# SCH_pie-day-pcb_2024-03-26.net
KiCad netlist of a schematic drawn in EasyEDA
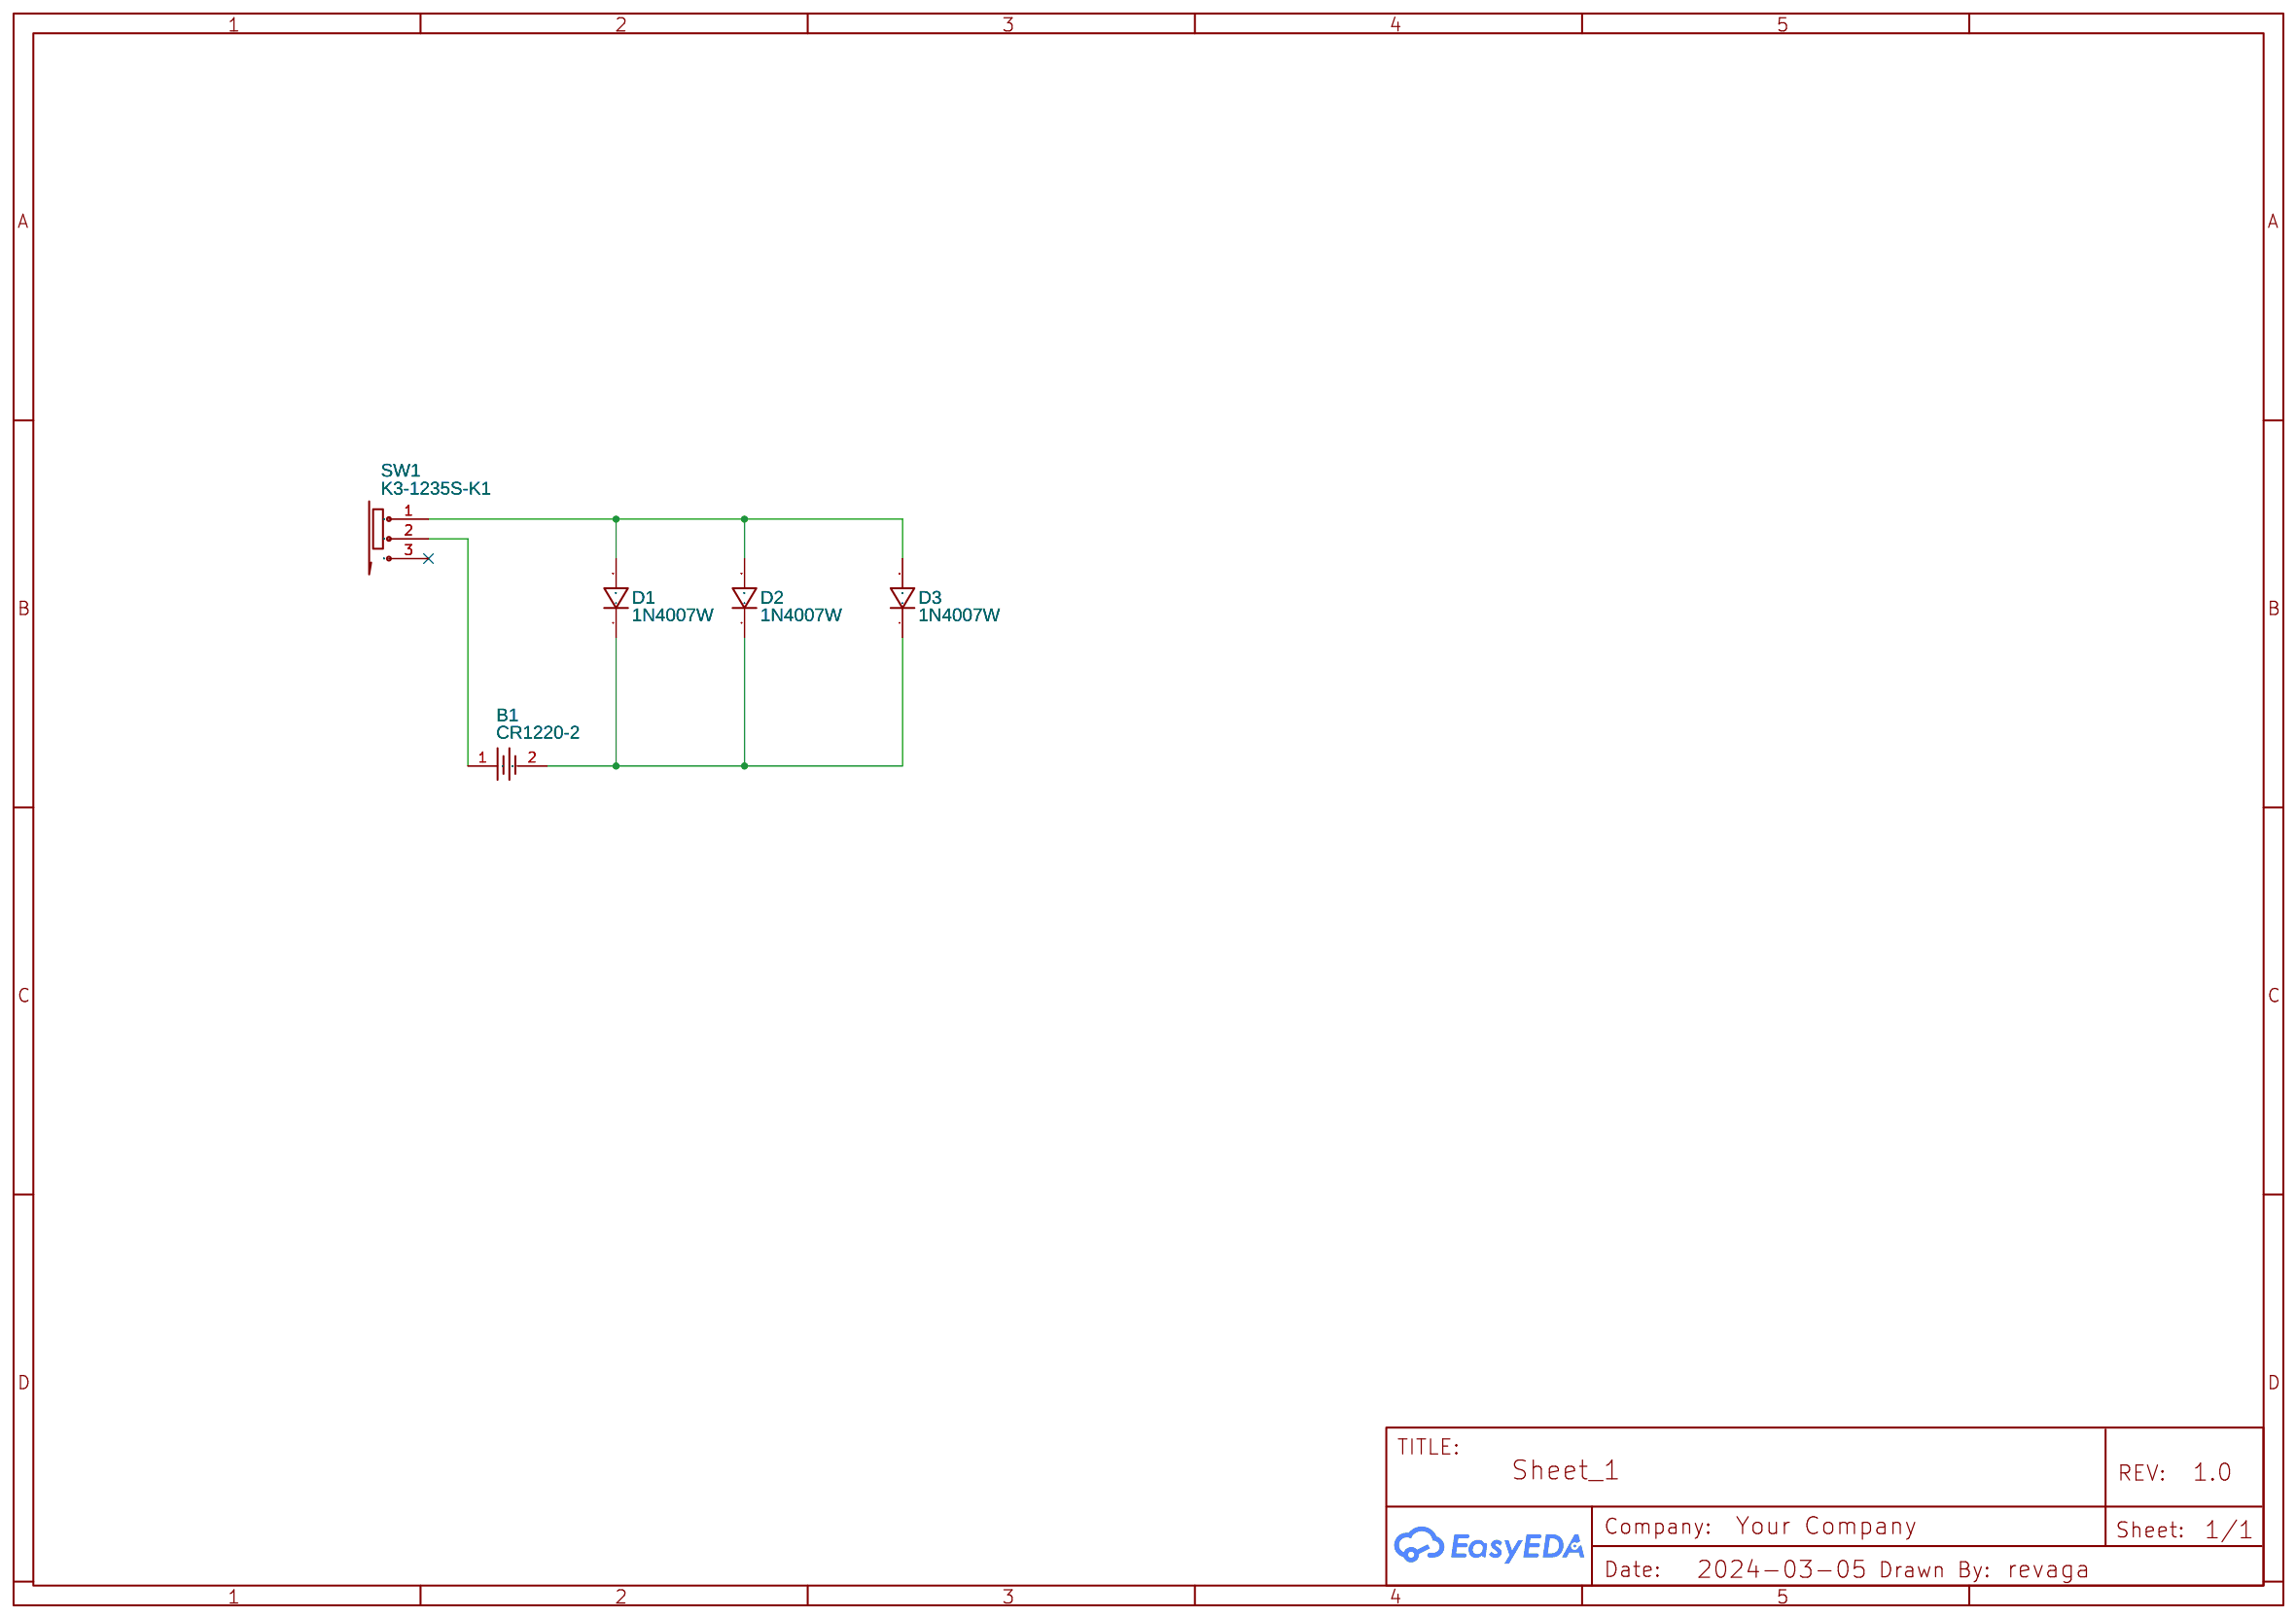
[diagram p0: schematic sheet]

(export (version "E")
  (design (tool "Eeschema 10.0.6"))
  (components
    (comp (ref "B1")
      (value "CR1220-2")
      (fields (field (name "Manufacturer") "Q&J"))
      (libsource (lib "") (part "CR1220-2"))
    )
    (comp (ref "D1")
      (value "1N4007W")
      (fields (field (name "Manufacturer") "BLUE ROCKET"))
      (libsource (lib "") (part "1N4007W"))
    )
    (comp (ref "D2")
      (value "1N4007W")
      (fields (field (name "Manufacturer") "BLUE ROCKET"))
      (libsource (lib "") (part "1N4007W"))
    )
    (comp (ref "D3")
      (value "1N4007W")
      (fields (field (name "Manufacturer") "BLUE ROCKET"))
      (libsource (lib "") (part "1N4007W"))
    )
    (comp (ref "SW1")
      (value "K3-1235S-K1")
      (fields (field (name "Manufacturer") "韩国韩荣"))
      (libsource (lib "") (part "K3-1235S-K1"))
    )
  )
  (nets
    (net (code "1") (name "Net-(B1-Pad1)") (class "Default")
      (node (ref "B1") (pin "1") (pinfunction "1_1") (pintype "input"))
      (node (ref "SW1") (pin "2") (pinfunction "2_2") (pintype "unspecified"))
    )
    (net (code "2") (name "Net-(B1-Pad2)") (class "Default")
      (node (ref "B1") (pin "2") (pinfunction "2_2") (pintype "input"))
      (node (ref "D1") (pin "1") (pinfunction "1_1") (pintype "unspecified"))
      (node (ref "D2") (pin "1") (pinfunction "1_1") (pintype "unspecified"))
      (node (ref "D3") (pin "1") (pinfunction "1_1") (pintype "unspecified"))
    )
    (net (code "3") (name "Net-(D1-Pad2)") (class "Default")
      (node (ref "D1") (pin "2") (pinfunction "2_2") (pintype "unspecified"))
      (node (ref "D2") (pin "2") (pinfunction "2_2") (pintype "unspecified"))
      (node (ref "D3") (pin "2") (pinfunction "2_2") (pintype "unspecified"))
      (node (ref "SW1") (pin "1") (pinfunction "1_1") (pintype "unspecified"))
    )
    (net (code "4") (name "unconnected-(SW1-Pad3)") (class "Default")
      (node (ref "SW1") (pin "3") (pinfunction "3_3") (pintype "unspecified+no_connect"))
    )
  )
)
